# v0.net
KiCad netlist of a schematic drawn in EAGLE
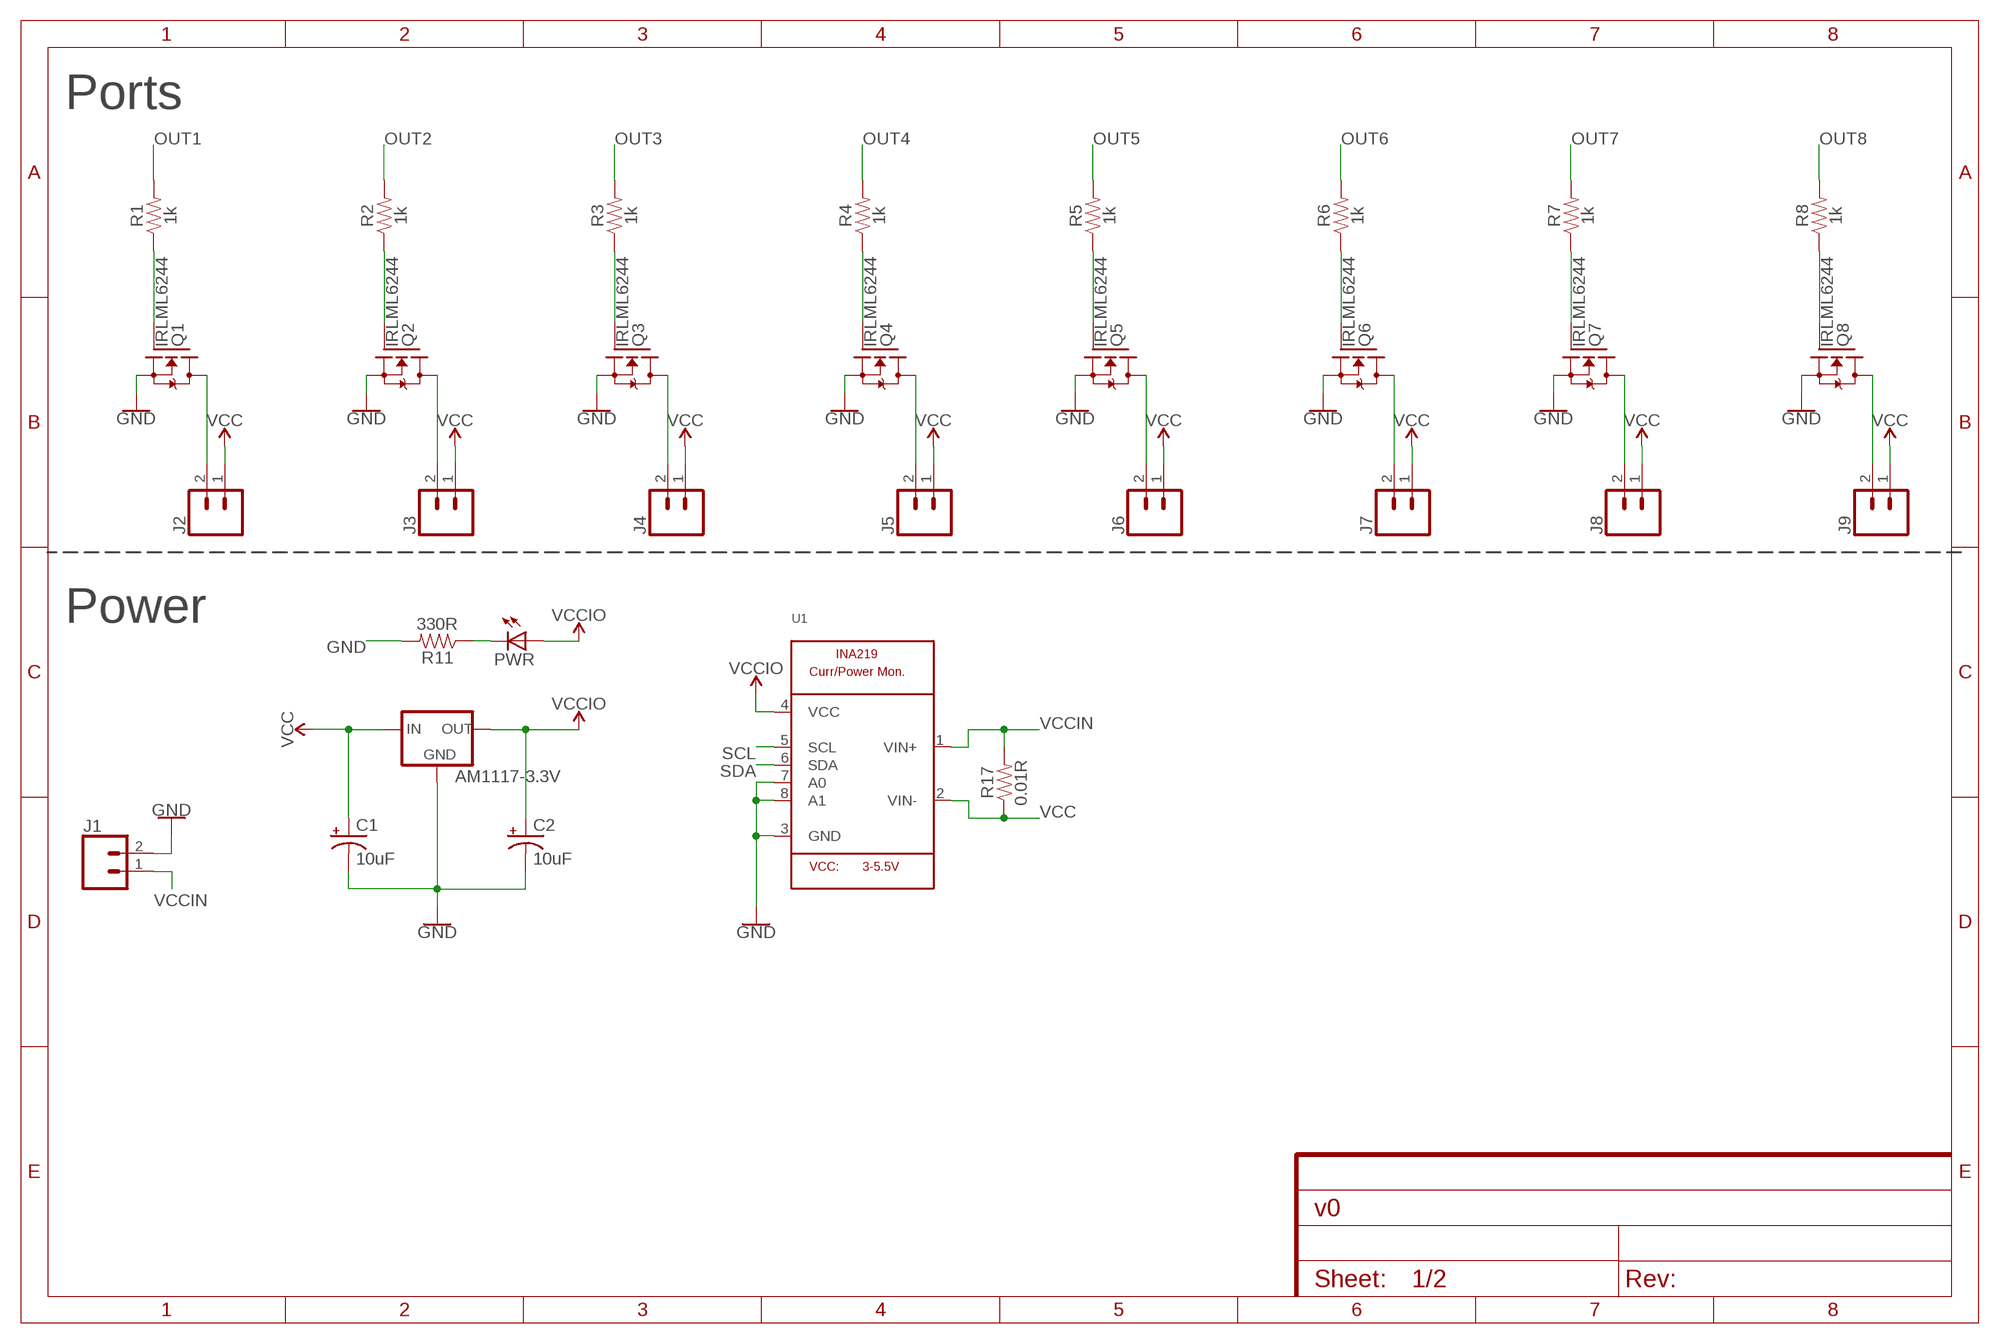
[diagram p0: schematic, sheet 1]
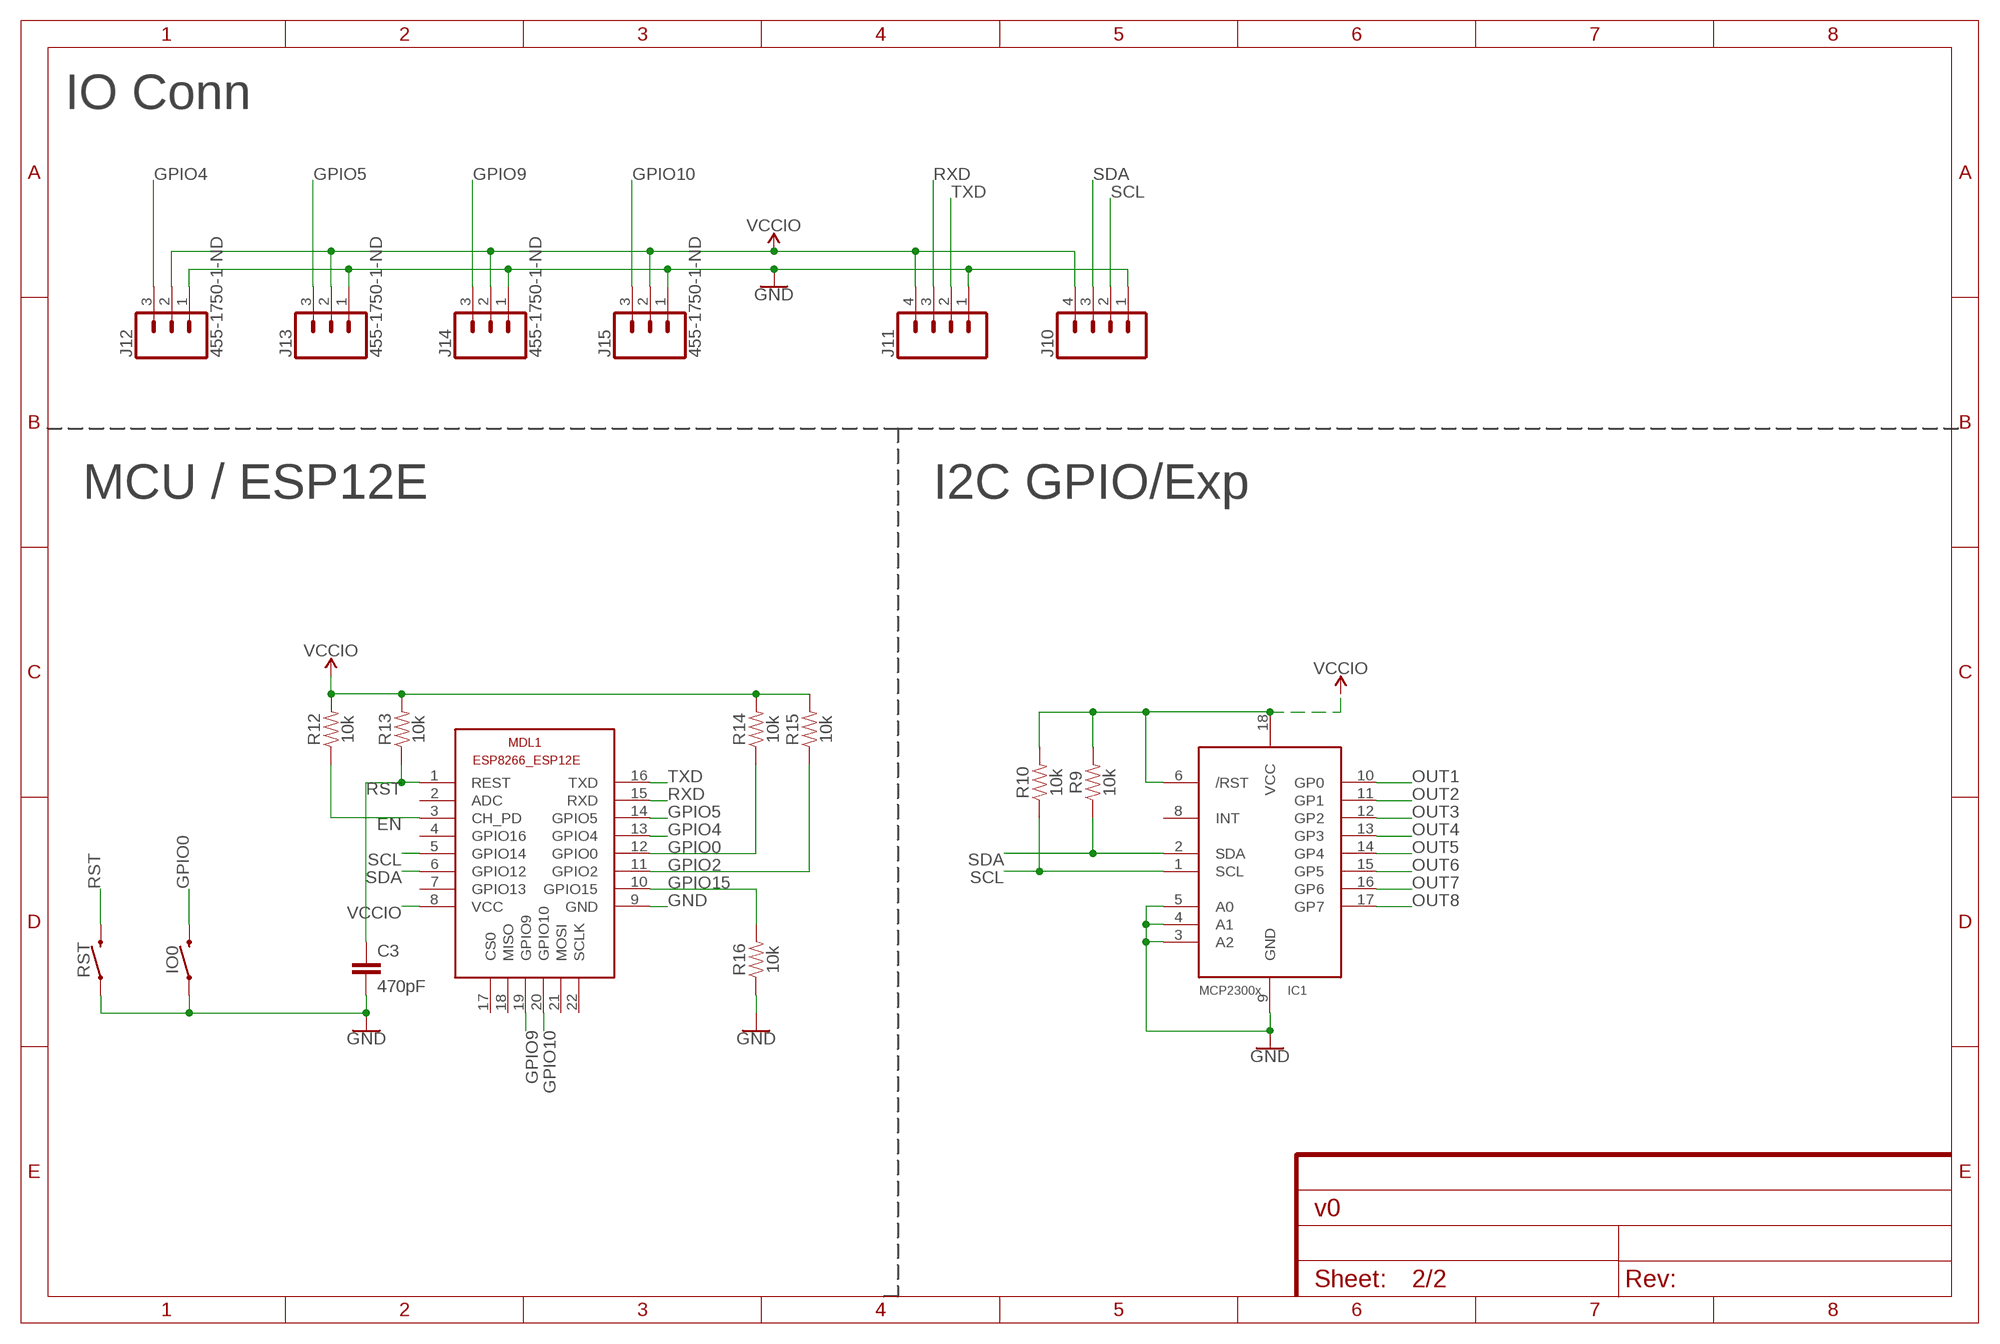
[diagram p1: schematic, sheet 2]

(export (version "E")
  (design (tool "Eeschema 10.0.6"))
  (components
    (comp (ref "C3")
      (value "470pF")
      (footprint "eagle-import:0805")
      (libsource (lib "eagle-import") (part "1.0UF-0805-25V-(+80/-20%)"))
    )
    (comp (ref "IC1")
      (value "MCP23008/SO")
      (footprint "eagle-import:SO18W")
      (libsource (lib "eagle-import") (part "MCP23008/SO"))
    )
    (comp (ref "IO0")
      (value "MOMENTARY-SWITCH-SPST-SMD-6.0X3.5MM")
      (footprint "eagle-import:TACTILE_SWITCH_SMD_6.0X3.5MM")
      (libsource (lib "eagle-import") (part "MOMENTARY-SWITCH-SPST-SMD-6.0X3.5MM"))
    )
    (comp (ref "J10")
      (value "CONN_04PTH")
      (footprint "eagle-import:1X04")
      (libsource (lib "eagle-import") (part "CONN_04PTH"))
    )
    (comp (ref "J11")
      (value "CONN_04PTH")
      (footprint "eagle-import:1X04")
      (libsource (lib "eagle-import") (part "CONN_04PTH"))
    )
    (comp (ref "J12")
      (value "455-1750-1-ND")
      (footprint "eagle-import:1X03")
      (libsource (lib "eagle-import") (part "CONN_03"))
    )
    (comp (ref "J13")
      (value "455-1750-1-ND")
      (footprint "eagle-import:1X03")
      (libsource (lib "eagle-import") (part "CONN_03"))
    )
    (comp (ref "J14")
      (value "455-1750-1-ND")
      (footprint "eagle-import:1X03")
      (libsource (lib "eagle-import") (part "CONN_03"))
    )
    (comp (ref "J15")
      (value "455-1750-1-ND")
      (footprint "eagle-import:1X03")
      (libsource (lib "eagle-import") (part "CONN_03"))
    )
    (comp (ref "MDL1")
      (value "ESP8266-12EESP8266-ESP12E")
      (footprint "eagle-import:ESP8266-ESP12E")
      (libsource (lib "eagle-import") (part "ESP8266-12EESP8266-ESP12E"))
    )
    (comp (ref "R9")
      (value "10k")
      (footprint "eagle-import:0805")
      (libsource (lib "eagle-import") (part "RESISTOR0805"))
    )
    (comp (ref "R10")
      (value "10k")
      (footprint "eagle-import:0805")
      (libsource (lib "eagle-import") (part "RESISTOR0805"))
    )
    (comp (ref "R12")
      (value "10k")
      (footprint "eagle-import:0805")
      (libsource (lib "eagle-import") (part "RESISTOR0805"))
    )
    (comp (ref "R13")
      (value "10k")
      (footprint "eagle-import:0805")
      (libsource (lib "eagle-import") (part "RESISTOR0805"))
    )
    (comp (ref "R14")
      (value "10k")
      (footprint "eagle-import:0805")
      (libsource (lib "eagle-import") (part "RESISTOR0805"))
    )
    (comp (ref "R15")
      (value "10k")
      (footprint "eagle-import:0805")
      (libsource (lib "eagle-import") (part "RESISTOR0805"))
    )
    (comp (ref "R16")
      (value "10k")
      (footprint "eagle-import:0805")
      (libsource (lib "eagle-import") (part "RESISTOR0805"))
    )
    (comp (ref "RST")
      (value "MOMENTARY-SWITCH-SPST-SMD-6.0X3.5MM")
      (footprint "eagle-import:TACTILE_SWITCH_SMD_6.0X3.5MM")
      (libsource (lib "eagle-import") (part "MOMENTARY-SWITCH-SPST-SMD-6.0X3.5MM"))
    )
    (comp (ref "AM1117-3.3V")
      (value "V_REG_LD1117VXXLD1117-SMD")
      (footprint "eagle-import:SOT223")
      (libsource (lib "eagle-import") (part "V_REG_LD1117VXXLD1117-SMD"))
    )
    (comp (ref "C1")
      (value "10uF")
      (footprint "eagle-import:EIA3216")
      (libsource (lib "eagle-import") (part "10UF-TANT"))
    )
    (comp (ref "C2")
      (value "10uF")
      (footprint "eagle-import:EIA3216")
      (libsource (lib "eagle-import") (part "10UF-TANT"))
    )
    (comp (ref "J1")
      (value "CONN_025MM")
      (footprint "eagle-import:SCREWTERMINAL-5MM-2")
      (libsource (lib "eagle-import") (part "CONN_025MM"))
    )
    (comp (ref "J2")
      (value "CONN_025MM")
      (footprint "eagle-import:SCREWTERMINAL-5MM-2")
      (fields (field (name "SPICEPREFIX") "B"))
      (libsource (lib "eagle-import") (part "CONN_025MM"))
    )
    (comp (ref "J3")
      (value "CONN_025MM")
      (footprint "eagle-import:SCREWTERMINAL-5MM-2")
      (libsource (lib "eagle-import") (part "CONN_025MM"))
    )
    (comp (ref "J4")
      (value "CONN_025MM")
      (footprint "eagle-import:SCREWTERMINAL-5MM-2")
      (libsource (lib "eagle-import") (part "CONN_025MM"))
    )
    (comp (ref "J5")
      (value "CONN_025MM")
      (footprint "eagle-import:SCREWTERMINAL-5MM-2")
      (libsource (lib "eagle-import") (part "CONN_025MM"))
    )
    (comp (ref "J6")
      (value "CONN_025MM")
      (footprint "eagle-import:SCREWTERMINAL-5MM-2")
      (libsource (lib "eagle-import") (part "CONN_025MM"))
    )
    (comp (ref "J7")
      (value "CONN_025MM")
      (footprint "eagle-import:SCREWTERMINAL-5MM-2")
      (libsource (lib "eagle-import") (part "CONN_025MM"))
    )
    (comp (ref "J8")
      (value "CONN_025MM")
      (footprint "eagle-import:SCREWTERMINAL-5MM-2")
      (libsource (lib "eagle-import") (part "CONN_025MM"))
    )
    (comp (ref "J9")
      (value "CONN_025MM")
      (footprint "eagle-import:SCREWTERMINAL-5MM-2")
      (libsource (lib "eagle-import") (part "CONN_025MM"))
    )
    (comp (ref "PWR")
      (value "LEDCHIP-LED0805")
      (footprint "eagle-import:CHIP-LED0805")
      (libsource (lib "eagle-import") (part "LEDCHIP-LED0805"))
    )
    (comp (ref "Q1")
      (value "IRLML6244")
      (footprint "eagle-import:SOT23")
      (fields
        (field (name "MF") "Internat. Rectifier")
        (field (name "MPN") "IRLML6244TRPbF")
        (field (name "SPICEPREFIX") "Q")
      )
      (libsource (lib "eagle-import") (part "IRLML6244"))
    )
    (comp (ref "Q2")
      (value "IRLML6244")
      (footprint "eagle-import:SOT23")
      (fields (field (name "MF") "Internat. Rectifier") (field (name "MPN") "IRLML6244TRPbF"))
      (libsource (lib "eagle-import") (part "IRLML6244"))
    )
    (comp (ref "Q3")
      (value "IRLML6244")
      (footprint "eagle-import:SOT23")
      (fields (field (name "MF") "Internat. Rectifier") (field (name "MPN") "IRLML6244TRPbF"))
      (libsource (lib "eagle-import") (part "IRLML6244"))
    )
    (comp (ref "Q4")
      (value "IRLML6244")
      (footprint "eagle-import:SOT23")
      (fields (field (name "MF") "Internat. Rectifier") (field (name "MPN") "IRLML6244TRPbF"))
      (libsource (lib "eagle-import") (part "IRLML6244"))
    )
    (comp (ref "Q5")
      (value "IRLML6244")
      (footprint "eagle-import:SOT23")
      (fields (field (name "MF") "Internat. Rectifier") (field (name "MPN") "IRLML6244TRPbF"))
      (libsource (lib "eagle-import") (part "IRLML6244"))
    )
    (comp (ref "Q6")
      (value "IRLML6244")
      (footprint "eagle-import:SOT23")
      (fields (field (name "MF") "Internat. Rectifier") (field (name "MPN") "IRLML6244TRPbF"))
      (libsource (lib "eagle-import") (part "IRLML6244"))
    )
    (comp (ref "Q7")
      (value "IRLML6244")
      (footprint "eagle-import:SOT23")
      (fields (field (name "MF") "Internat. Rectifier") (field (name "MPN") "IRLML6244TRPbF"))
      (libsource (lib "eagle-import") (part "IRLML6244"))
    )
    (comp (ref "Q8")
      (value "IRLML6244")
      (footprint "eagle-import:SOT23")
      (fields (field (name "MF") "Internat. Rectifier") (field (name "MPN") "IRLML6244TRPbF"))
      (libsource (lib "eagle-import") (part "IRLML6244"))
    )
    (comp (ref "R1")
      (value "1k")
      (footprint "eagle-import:0805")
      (fields (field (name "SPICEPREFIX") "R"))
      (libsource (lib "eagle-import") (part "RESISTOR0805"))
    )
    (comp (ref "R2")
      (value "1k")
      (footprint "eagle-import:0805")
      (libsource (lib "eagle-import") (part "RESISTOR0805"))
    )
    (comp (ref "R3")
      (value "1k")
      (footprint "eagle-import:0805")
      (libsource (lib "eagle-import") (part "RESISTOR0805"))
    )
    (comp (ref "R4")
      (value "1k")
      (footprint "eagle-import:0805")
      (libsource (lib "eagle-import") (part "RESISTOR0805"))
    )
    (comp (ref "R5")
      (value "1k")
      (footprint "eagle-import:0805")
      (libsource (lib "eagle-import") (part "RESISTOR0805"))
    )
    (comp (ref "R6")
      (value "1k")
      (footprint "eagle-import:0805")
      (libsource (lib "eagle-import") (part "RESISTOR0805"))
    )
    (comp (ref "R7")
      (value "1k")
      (footprint "eagle-import:0805")
      (libsource (lib "eagle-import") (part "RESISTOR0805"))
    )
    (comp (ref "R8")
      (value "1k")
      (footprint "eagle-import:0805")
      (libsource (lib "eagle-import") (part "RESISTOR0805"))
    )
    (comp (ref "R11")
      (value "330R")
      (footprint "eagle-import:0805")
      (libsource (lib "eagle-import") (part "RESISTOR0805"))
    )
    (comp (ref "R17")
      (value "0.01R")
      (footprint "eagle-import:2512")
      (libsource (lib "eagle-import") (part "0.05OHM-2512-3W-1%"))
    )
    (comp (ref "U1")
      (value "INA219")
      (footprint "eagle-import:SOT23-8")
      (libsource (lib "eagle-import") (part "INA219"))
    )
  )
  (nets
    (net (code "1") (name "EN") (class "Default")
      (node (ref "MDL1") (pin "3") (pinfunction "CH_PD_3") (pintype "bidirectional"))
      (node (ref "R12") (pin "1") (pinfunction "1_1") (pintype "passive"))
    )
    (net (code "2") (name "GND") (class "Default")
      (node (ref "AM1117-3.3V") (pin "1") (pinfunction "GND_1") (pintype "input"))
      (node (ref "C1") (pin "C") (pinfunction "-_C") (pintype "passive"))
      (node (ref "C2") (pin "C") (pinfunction "-_C") (pintype "passive"))
      (node (ref "C3") (pin "2") (pinfunction "2_2") (pintype "passive"))
      (node (ref "IC1") (pin "3") (pinfunction "A2_3") (pintype "input"))
      (node (ref "IC1") (pin "4") (pinfunction "A1_4") (pintype "input"))
      (node (ref "IC1") (pin "5") (pinfunction "A0_5") (pintype "input"))
      (node (ref "IC1") (pin "9") (pinfunction "GND_9") (pintype "power_in"))
      (node (ref "IO0") (pin "1") (pinfunction "1_1") (pintype "passive"))
      (node (ref "J1") (pin "2") (pinfunction "2_2") (pintype "passive"))
      (node (ref "J10") (pin "1") (pinfunction "1_1") (pintype "passive"))
      (node (ref "J11") (pin "1") (pinfunction "1_1") (pintype "passive"))
      (node (ref "J12") (pin "1") (pinfunction "1_1") (pintype "passive"))
      (node (ref "J13") (pin "1") (pinfunction "1_1") (pintype "passive"))
      (node (ref "J14") (pin "1") (pinfunction "1_1") (pintype "passive"))
      (node (ref "J15") (pin "1") (pinfunction "1_1") (pintype "passive"))
      (node (ref "MDL1") (pin "9") (pinfunction "GND_9") (pintype "bidirectional"))
      (node (ref "Q1") (pin "2") (pinfunction "S_2") (pintype "passive"))
      (node (ref "Q2") (pin "2") (pinfunction "S_2") (pintype "passive"))
      (node (ref "Q3") (pin "2") (pinfunction "S_2") (pintype "passive"))
      (node (ref "Q4") (pin "2") (pinfunction "S_2") (pintype "passive"))
      (node (ref "Q5") (pin "2") (pinfunction "S_2") (pintype "passive"))
      (node (ref "Q6") (pin "2") (pinfunction "S_2") (pintype "passive"))
      (node (ref "Q7") (pin "2") (pinfunction "S_2") (pintype "passive"))
      (node (ref "Q8") (pin "2") (pinfunction "S_2") (pintype "passive"))
      (node (ref "R11") (pin "2") (pinfunction "2_2") (pintype "passive"))
      (node (ref "R16") (pin "1") (pinfunction "1_1") (pintype "passive"))
      (node (ref "RST") (pin "1") (pinfunction "1_1") (pintype "passive"))
      (node (ref "U1") (pin "3") (pinfunction "GND_3") (pintype "bidirectional"))
      (node (ref "U1") (pin "7") (pinfunction "A0_7") (pintype "bidirectional"))
      (node (ref "U1") (pin "8") (pinfunction "A1_8") (pintype "bidirectional"))
    )
    (net (code "3") (name "GPIO0") (class "Default")
      (node (ref "IO0") (pin "2") (pinfunction "2_2") (pintype "passive"))
      (node (ref "MDL1") (pin "12") (pinfunction "GPIO0_12") (pintype "bidirectional"))
      (node (ref "R14") (pin "1") (pinfunction "1_1") (pintype "passive"))
    )
    (net (code "4") (name "GPIO2") (class "Default")
      (node (ref "MDL1") (pin "11") (pinfunction "GPIO2_11") (pintype "bidirectional"))
      (node (ref "R15") (pin "1") (pinfunction "1_1") (pintype "passive"))
    )
    (net (code "5") (name "GPIO4") (class "Default")
      (node (ref "J12") (pin "3") (pinfunction "3_3") (pintype "passive"))
      (node (ref "MDL1") (pin "13") (pinfunction "GPIO4_13") (pintype "bidirectional"))
    )
    (net (code "6") (name "GPIO5") (class "Default")
      (node (ref "J13") (pin "3") (pinfunction "3_3") (pintype "passive"))
      (node (ref "MDL1") (pin "14") (pinfunction "GPIO5_14") (pintype "bidirectional"))
    )
    (net (code "7") (name "GPIO9") (class "Default")
      (node (ref "J14") (pin "3") (pinfunction "3_3") (pintype "passive"))
      (node (ref "MDL1") (pin "19") (pinfunction "GPIO9_19") (pintype "bidirectional"))
    )
    (net (code "8") (name "GPIO10") (class "Default")
      (node (ref "J15") (pin "3") (pinfunction "3_3") (pintype "passive"))
      (node (ref "MDL1") (pin "20") (pinfunction "GPIO10_20") (pintype "bidirectional"))
    )
    (net (code "9") (name "GPIO15") (class "Default")
      (node (ref "MDL1") (pin "10") (pinfunction "GPIO15_10") (pintype "bidirectional"))
      (node (ref "R16") (pin "2") (pinfunction "2_2") (pintype "passive"))
    )
    (net (code "10") (name "Net-(PWR-PadC)") (class "Default")
      (node (ref "PWR") (pin "C") (pinfunction "C_C") (pintype "passive"))
      (node (ref "R11") (pin "1") (pinfunction "1_1") (pintype "passive"))
    )
    (net (code "11") (name "Net-(Q1-D)") (class "Default")
      (node (ref "J2") (pin "2") (pinfunction "2_2") (pintype "passive"))
      (node (ref "Q1") (pin "3") (pinfunction "D_3") (pintype "passive"))
    )
    (net (code "12") (name "Net-(Q1-G)") (class "Default")
      (node (ref "Q1") (pin "1") (pinfunction "G_1") (pintype "passive"))
      (node (ref "R1") (pin "1") (pinfunction "1_1") (pintype "passive"))
    )
    (net (code "13") (name "Net-(Q2-D)") (class "Default")
      (node (ref "J3") (pin "2") (pinfunction "2_2") (pintype "passive"))
      (node (ref "Q2") (pin "3") (pinfunction "D_3") (pintype "passive"))
    )
    (net (code "14") (name "Net-(Q2-G)") (class "Default")
      (node (ref "Q2") (pin "1") (pinfunction "G_1") (pintype "passive"))
      (node (ref "R2") (pin "1") (pinfunction "1_1") (pintype "passive"))
    )
    (net (code "15") (name "Net-(Q3-D)") (class "Default")
      (node (ref "J4") (pin "2") (pinfunction "2_2") (pintype "passive"))
      (node (ref "Q3") (pin "3") (pinfunction "D_3") (pintype "passive"))
    )
    (net (code "16") (name "Net-(Q3-G)") (class "Default")
      (node (ref "Q3") (pin "1") (pinfunction "G_1") (pintype "passive"))
      (node (ref "R3") (pin "1") (pinfunction "1_1") (pintype "passive"))
    )
    (net (code "17") (name "Net-(Q4-D)") (class "Default")
      (node (ref "J5") (pin "2") (pinfunction "2_2") (pintype "passive"))
      (node (ref "Q4") (pin "3") (pinfunction "D_3") (pintype "passive"))
    )
    (net (code "18") (name "Net-(Q4-G)") (class "Default")
      (node (ref "Q4") (pin "1") (pinfunction "G_1") (pintype "passive"))
      (node (ref "R4") (pin "1") (pinfunction "1_1") (pintype "passive"))
    )
    (net (code "19") (name "Net-(Q5-D)") (class "Default")
      (node (ref "J6") (pin "2") (pinfunction "2_2") (pintype "passive"))
      (node (ref "Q5") (pin "3") (pinfunction "D_3") (pintype "passive"))
    )
    (net (code "20") (name "Net-(Q5-G)") (class "Default")
      (node (ref "Q5") (pin "1") (pinfunction "G_1") (pintype "passive"))
      (node (ref "R5") (pin "1") (pinfunction "1_1") (pintype "passive"))
    )
    (net (code "21") (name "Net-(Q6-D)") (class "Default")
      (node (ref "J7") (pin "2") (pinfunction "2_2") (pintype "passive"))
      (node (ref "Q6") (pin "3") (pinfunction "D_3") (pintype "passive"))
    )
    (net (code "22") (name "Net-(Q6-G)") (class "Default")
      (node (ref "Q6") (pin "1") (pinfunction "G_1") (pintype "passive"))
      (node (ref "R6") (pin "1") (pinfunction "1_1") (pintype "passive"))
    )
    (net (code "23") (name "Net-(Q7-D)") (class "Default")
      (node (ref "J8") (pin "2") (pinfunction "2_2") (pintype "passive"))
      (node (ref "Q7") (pin "3") (pinfunction "D_3") (pintype "passive"))
    )
    (net (code "24") (name "Net-(Q7-G)") (class "Default")
      (node (ref "Q7") (pin "1") (pinfunction "G_1") (pintype "passive"))
      (node (ref "R7") (pin "1") (pinfunction "1_1") (pintype "passive"))
    )
    (net (code "25") (name "Net-(Q8-D)") (class "Default")
      (node (ref "J9") (pin "2") (pinfunction "2_2") (pintype "passive"))
      (node (ref "Q8") (pin "3") (pinfunction "D_3") (pintype "passive"))
    )
    (net (code "26") (name "Net-(Q8-G)") (class "Default")
      (node (ref "Q8") (pin "1") (pinfunction "G_1") (pintype "passive"))
      (node (ref "R8") (pin "1") (pinfunction "1_1") (pintype "passive"))
    )
    (net (code "27") (name "OUT1") (class "Default")
      (node (ref "IC1") (pin "10") (pinfunction "GP0_10") (pintype "bidirectional"))
      (node (ref "R1") (pin "2") (pinfunction "2_2") (pintype "passive"))
    )
    (net (code "28") (name "OUT2") (class "Default")
      (node (ref "IC1") (pin "11") (pinfunction "GP1_11") (pintype "bidirectional"))
      (node (ref "R2") (pin "2") (pinfunction "2_2") (pintype "passive"))
    )
    (net (code "29") (name "OUT3") (class "Default")
      (node (ref "IC1") (pin "12") (pinfunction "GP2_12") (pintype "bidirectional"))
      (node (ref "R3") (pin "2") (pinfunction "2_2") (pintype "passive"))
    )
    (net (code "30") (name "OUT4") (class "Default")
      (node (ref "IC1") (pin "13") (pinfunction "GP3_13") (pintype "bidirectional"))
      (node (ref "R4") (pin "2") (pinfunction "2_2") (pintype "passive"))
    )
    (net (code "31") (name "OUT5") (class "Default")
      (node (ref "IC1") (pin "14") (pinfunction "GP4_14") (pintype "bidirectional"))
      (node (ref "R5") (pin "2") (pinfunction "2_2") (pintype "passive"))
    )
    (net (code "32") (name "OUT6") (class "Default")
      (node (ref "IC1") (pin "15") (pinfunction "GP5_15") (pintype "bidirectional"))
      (node (ref "R6") (pin "2") (pinfunction "2_2") (pintype "passive"))
    )
    (net (code "33") (name "OUT7") (class "Default")
      (node (ref "IC1") (pin "16") (pinfunction "GP6_16") (pintype "bidirectional"))
      (node (ref "R7") (pin "2") (pinfunction "2_2") (pintype "passive"))
    )
    (net (code "34") (name "OUT8") (class "Default")
      (node (ref "IC1") (pin "17") (pinfunction "GP7_17") (pintype "bidirectional"))
      (node (ref "R8") (pin "2") (pinfunction "2_2") (pintype "passive"))
    )
    (net (code "35") (name "RST") (class "Default")
      (node (ref "C3") (pin "1") (pinfunction "1_1") (pintype "passive"))
      (node (ref "MDL1") (pin "1") (pinfunction "REST_1") (pintype "bidirectional"))
      (node (ref "R13") (pin "1") (pinfunction "1_1") (pintype "passive"))
      (node (ref "RST") (pin "2") (pinfunction "2_2") (pintype "passive"))
    )
    (net (code "36") (name "RXD") (class "Default")
      (node (ref "J11") (pin "3") (pinfunction "3_3") (pintype "passive"))
      (node (ref "MDL1") (pin "15") (pinfunction "RXD_15") (pintype "bidirectional"))
    )
    (net (code "37") (name "SCL") (class "Default")
      (node (ref "IC1") (pin "1") (pinfunction "SCL_1") (pintype "bidirectional"))
      (node (ref "J10") (pin "2") (pinfunction "2_2") (pintype "passive"))
      (node (ref "MDL1") (pin "5") (pinfunction "GPIO14_5") (pintype "bidirectional"))
      (node (ref "R10") (pin "1") (pinfunction "1_1") (pintype "passive"))
      (node (ref "U1") (pin "5") (pinfunction "SCL_5") (pintype "bidirectional"))
    )
    (net (code "38") (name "SDA") (class "Default")
      (node (ref "IC1") (pin "2") (pinfunction "SDA_2") (pintype "bidirectional"))
      (node (ref "J10") (pin "3") (pinfunction "3_3") (pintype "passive"))
      (node (ref "MDL1") (pin "6") (pinfunction "GPIO12_6") (pintype "bidirectional"))
      (node (ref "R9") (pin "1") (pinfunction "1_1") (pintype "passive"))
      (node (ref "U1") (pin "6") (pinfunction "SDA_6") (pintype "bidirectional"))
    )
    (net (code "39") (name "TXD") (class "Default")
      (node (ref "J11") (pin "2") (pinfunction "2_2") (pintype "passive"))
      (node (ref "MDL1") (pin "16") (pinfunction "TXD_16") (pintype "bidirectional"))
    )
    (net (code "40") (name "VCC") (class "Default")
      (node (ref "AM1117-3.3V") (pin "3") (pinfunction "IN_3") (pintype "input"))
      (node (ref "C1") (pin "A") (pinfunction "+_A") (pintype "passive"))
      (node (ref "J2") (pin "1") (pinfunction "1_1") (pintype "passive"))
      (node (ref "J3") (pin "1") (pinfunction "1_1") (pintype "passive"))
      (node (ref "J4") (pin "1") (pinfunction "1_1") (pintype "passive"))
      (node (ref "J5") (pin "1") (pinfunction "1_1") (pintype "passive"))
      (node (ref "J6") (pin "1") (pinfunction "1_1") (pintype "passive"))
      (node (ref "J7") (pin "1") (pinfunction "1_1") (pintype "passive"))
      (node (ref "J8") (pin "1") (pinfunction "1_1") (pintype "passive"))
      (node (ref "J9") (pin "1") (pinfunction "1_1") (pintype "passive"))
      (node (ref "R17") (pin "P$1") (pinfunction "1_P$1") (pintype "passive"))
      (node (ref "U1") (pin "2") (pinfunction "VIN-_2") (pintype "bidirectional"))
    )
    (net (code "41") (name "VCCIN") (class "Default")
      (node (ref "J1") (pin "1") (pinfunction "1_1") (pintype "passive"))
      (node (ref "R17") (pin "P$2") (pinfunction "2_P$2") (pintype "passive"))
      (node (ref "U1") (pin "1") (pinfunction "VIN+_1") (pintype "bidirectional"))
    )
    (net (code "42") (name "VCCIO") (class "Default")
      (node (ref "AM1117-3.3V") (pin "2") (pinfunction "OUT_2") (pintype "passive"))
      (node (ref "C2") (pin "A") (pinfunction "+_A") (pintype "passive"))
      (node (ref "IC1") (pin "18") (pinfunction "VCC_18") (pintype "power_in"))
      (node (ref "IC1") (pin "6") (pinfunction "/RST_6") (pintype "input"))
      (node (ref "J10") (pin "4") (pinfunction "4_4") (pintype "passive"))
      (node (ref "J11") (pin "4") (pinfunction "4_4") (pintype "passive"))
      (node (ref "J12") (pin "2") (pinfunction "2_2") (pintype "passive"))
      (node (ref "J13") (pin "2") (pinfunction "2_2") (pintype "passive"))
      (node (ref "J14") (pin "2") (pinfunction "2_2") (pintype "passive"))
      (node (ref "J15") (pin "2") (pinfunction "2_2") (pintype "passive"))
      (node (ref "MDL1") (pin "8") (pinfunction "VCC_8") (pintype "bidirectional"))
      (node (ref "PWR") (pin "A") (pinfunction "A_A") (pintype "passive"))
      (node (ref "R10") (pin "2") (pinfunction "2_2") (pintype "passive"))
      (node (ref "R12") (pin "2") (pinfunction "2_2") (pintype "passive"))
      (node (ref "R13") (pin "2") (pinfunction "2_2") (pintype "passive"))
      (node (ref "R14") (pin "2") (pinfunction "2_2") (pintype "passive"))
      (node (ref "R15") (pin "2") (pinfunction "2_2") (pintype "passive"))
      (node (ref "R9") (pin "2") (pinfunction "2_2") (pintype "passive"))
      (node (ref "U1") (pin "4") (pinfunction "VCC_4") (pintype "bidirectional"))
    )
    (net (code "43") (name "unconnected-(IC1-INT-Pad8)") (class "Default")
      (node (ref "IC1") (pin "8") (pinfunction "INT_8") (pintype "output"))
    )
    (net (code "44") (name "unconnected-(MDL1-ADC-Pad2)") (class "Default")
      (node (ref "MDL1") (pin "2") (pinfunction "ADC_2") (pintype "bidirectional"))
    )
    (net (code "45") (name "unconnected-(MDL1-CS0-Pad17)") (class "Default")
      (node (ref "MDL1") (pin "17") (pinfunction "CS0_17") (pintype "bidirectional"))
    )
    (net (code "46") (name "unconnected-(MDL1-GPIO13-Pad7)") (class "Default")
      (node (ref "MDL1") (pin "7") (pinfunction "GPIO13_7") (pintype "bidirectional"))
    )
    (net (code "47") (name "unconnected-(MDL1-GPIO16-Pad4)") (class "Default")
      (node (ref "MDL1") (pin "4") (pinfunction "GPIO16_4") (pintype "bidirectional"))
    )
    (net (code "48") (name "unconnected-(MDL1-MISO-Pad18)") (class "Default")
      (node (ref "MDL1") (pin "18") (pinfunction "MISO_18") (pintype "bidirectional"))
    )
    (net (code "49") (name "unconnected-(MDL1-MOSI-Pad21)") (class "Default")
      (node (ref "MDL1") (pin "21") (pinfunction "MOSI_21") (pintype "bidirectional"))
    )
    (net (code "50") (name "unconnected-(MDL1-SCLK-Pad22)") (class "Default")
      (node (ref "MDL1") (pin "22") (pinfunction "SCLK_22") (pintype "bidirectional"))
    )
  )
)
